# pulseox_brakeout_LCD_SCH.net
KiCad netlist of a schematic drawn in Altium Designer
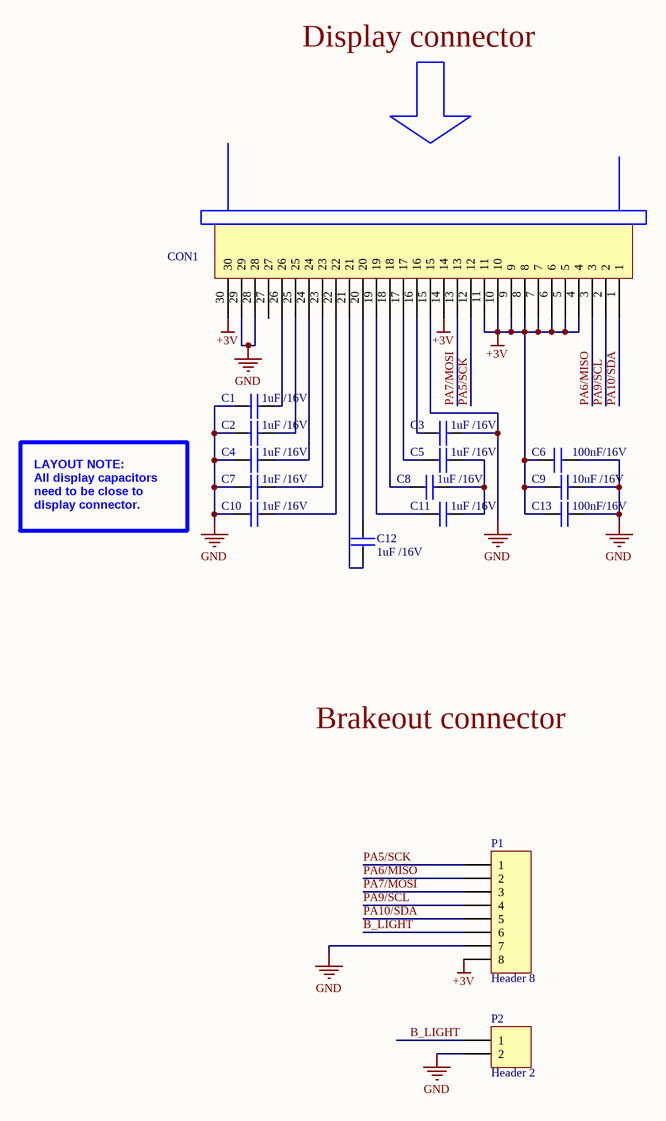
[diagram p0: pulseox_brakeout_LCD_SCH.SchDoc]

(export (version "E")
  (design (tool "Eeschema 10.0.6"))
  (components
    (comp (ref "C1")
      (value "1uF /16V")
      (footprint "CAP0805")
      (description "MURATA - GRM21BR71C105KA01L - CAP, MLCC, X7R, 1UF, 16V, 0805")
      (fields
        (field (name "MANUFACTURER") "MURATA")
        (field (name "MANUFACTURER PART NUMBER") "GRM21BR71C105KA01L")
      )
      (libsource (lib "Capacitors") (part "1uF /16V"))
    )
    (comp (ref "C2")
      (value "1uF /16V")
      (footprint "CAP0805")
      (description "MURATA - GRM21BR71C105KA01L - CAP, MLCC, X7R, 1UF, 16V, 0805")
      (fields
        (field (name "MANUFACTURER") "MURATA")
        (field (name "MANUFACTURER PART NUMBER") "GRM21BR71C105KA01L")
      )
      (libsource (lib "Capacitors") (part "1uF /16V"))
    )
    (comp (ref "C3")
      (value "1uF /16V")
      (footprint "CAP0805")
      (description "MURATA - GRM21BR71C105KA01L - CAP, MLCC, X7R, 1UF, 16V, 0805")
      (fields
        (field (name "MANUFACTURER") "MURATA")
        (field (name "MANUFACTURER PART NUMBER") "GRM21BR71C105KA01L")
      )
      (libsource (lib "Capacitors") (part "1uF /16V"))
    )
    (comp (ref "C4")
      (value "1uF /16V")
      (footprint "CAP0805")
      (description "MURATA - GRM21BR71C105KA01L - CAP, MLCC, X7R, 1UF, 16V, 0805")
      (fields
        (field (name "MANUFACTURER") "MURATA")
        (field (name "MANUFACTURER PART NUMBER") "GRM21BR71C105KA01L")
      )
      (libsource (lib "Capacitors") (part "1uF /16V"))
    )
    (comp (ref "C5")
      (value "1uF /16V")
      (footprint "CAP0805")
      (description "MURATA - GRM21BR71C105KA01L - CAP, MLCC, X7R, 1UF, 16V, 0805")
      (fields
        (field (name "MANUFACTURER") "MURATA")
        (field (name "MANUFACTURER PART NUMBER") "GRM21BR71C105KA01L")
      )
      (libsource (lib "Capacitors") (part "1uF /16V"))
    )
    (comp (ref "C6")
      (value "100nF/16V")
      (footprint "CAP0805")
      (description "MURATA - GRM219R71C104KA01D - CAP, MLCC, X7R, 0.1UF, 16V, 0805")
      (fields
        (field (name "MANUFACTURER") "MURATA")
        (field (name "MANUFACTURER PART NUMBER") "GRM219R71C104KA01D")
      )
      (libsource (lib "Capacitors") (part "100nF 16V 0805"))
    )
    (comp (ref "C7")
      (value "1uF /16V")
      (footprint "CAP0805")
      (description "MURATA - GRM21BR71C105KA01L - CAP, MLCC, X7R, 1UF, 16V, 0805")
      (fields
        (field (name "MANUFACTURER") "MURATA")
        (field (name "MANUFACTURER PART NUMBER") "GRM21BR71C105KA01L")
      )
      (libsource (lib "Capacitors") (part "1uF /16V"))
    )
    (comp (ref "C8")
      (value "1uF /16V")
      (footprint "CAP0805")
      (description "MURATA - GRM21BR71C105KA01L - CAP, MLCC, X7R, 1UF, 16V, 0805")
      (fields
        (field (name "MANUFACTURER") "MURATA")
        (field (name "MANUFACTURER PART NUMBER") "GRM21BR71C105KA01L")
      )
      (libsource (lib "Capacitors") (part "1uF /16V"))
    )
    (comp (ref "C9")
      (value "10uF /16V")
      (footprint "CAP0805")
      (description "TDK - CGA4J1X5R1C106K125AC - CAP, MLCC, X5R, 10UF, 16V, 0805")
      (fields
        (field (name "MANUFACTURER") "TDK")
        (field (name "MANUFACTURER PART NUMBER") "CGA4J1X5R1C106K125AC")
      )
      (libsource (lib "Capacitors") (part "10uF /16V"))
    )
    (comp (ref "C10")
      (value "1uF /16V")
      (footprint "CAP0805")
      (description "MURATA - GRM21BR71C105KA01L - CAP, MLCC, X7R, 1UF, 16V, 0805")
      (fields
        (field (name "MANUFACTURER") "MURATA")
        (field (name "MANUFACTURER PART NUMBER") "GRM21BR71C105KA01L")
      )
      (libsource (lib "Capacitors") (part "1uF /16V"))
    )
    (comp (ref "C11")
      (value "1uF /16V")
      (footprint "CAP0805")
      (description "MURATA - GRM21BR71C105KA01L - CAP, MLCC, X7R, 1UF, 16V, 0805")
      (fields
        (field (name "MANUFACTURER") "MURATA")
        (field (name "MANUFACTURER PART NUMBER") "GRM21BR71C105KA01L")
      )
      (libsource (lib "Capacitors") (part "1uF /16V"))
    )
    (comp (ref "C12")
      (value "1uF /16V")
      (footprint "CAP0805")
      (description "MURATA - GRM21BR71C105KA01L - CAP, MLCC, X7R, 1UF, 16V, 0805")
      (fields
        (field (name "MANUFACTURER") "MURATA")
        (field (name "MANUFACTURER PART NUMBER") "GRM21BR71C105KA01L")
      )
      (libsource (lib "Capacitors") (part "1uF /16V"))
    )
    (comp (ref "C13")
      (value "100nF/16V")
      (footprint "CAP0805")
      (description "MURATA - GRM219R71C104KA01D - CAP, MLCC, X7R, 0.1UF, 16V, 0805")
      (fields
        (field (name "MANUFACTURER") "MURATA")
        (field (name "MANUFACTURER PART NUMBER") "GRM219R71C104KA01D")
      )
      (libsource (lib "Capacitors") (part "100nF 16V 0805"))
    )
    (comp (ref "CON1")
      (value "3-1734592-0")
      (footprint "FPC P0.5mm SMT")
      (description "AMP - TE CONNECTIVITY - 3-1734592-0 - CONNECTOR, FFC / FPC, 0.5MM, 30WAY")
      (fields (field (name "MANUFACTURER") "AMP - TE CONNECTIVITY"))
      (libsource (lib "FFC-FPC board connectors") (part "3-1734592-0"))
    )
    (comp (ref "P1")
      (value "Header 8")
      (footprint "HDR1X8")
      (description "Header, 8-Pin")
      (fields (field (name "PUBLISHER") "Altium Limited"))
      (libsource (lib "Miscellaneous Connectors") (part "Header 8"))
    )
    (comp (ref "P2")
      (value "Header 2")
      (footprint "HDR1X2")
      (description "Header, 2-Pin")
      (fields (field (name "PUBLISHER") "Altium Limited"))
      (libsource (lib "Miscellaneous Connectors") (part "Header 2"))
    )
  )
  (nets
    (net (code "1") (name "+3V") (class "Default")
      (node (ref "C13") (pin "1") (pinfunction "1_1") (pintype "passive"))
      (node (ref "C6") (pin "1") (pinfunction "1_1") (pintype "passive"))
      (node (ref "C9") (pin "1") (pinfunction "1_1") (pintype "passive"))
      (node (ref "CON1") (pin "10") (pinfunction "10_10") (pintype "open_collector"))
      (node (ref "CON1") (pin "11") (pinfunction "11_11") (pintype "open_collector"))
      (node (ref "CON1") (pin "14") (pinfunction "14_14") (pintype "open_collector"))
      (node (ref "CON1") (pin "30") (pinfunction "30_30") (pintype "open_collector"))
      (node (ref "CON1") (pin "4") (pinfunction "4_4") (pintype "open_collector"))
      (node (ref "CON1") (pin "5") (pinfunction "5_5") (pintype "open_collector"))
      (node (ref "CON1") (pin "6") (pinfunction "6_6") (pintype "open_collector"))
      (node (ref "CON1") (pin "7") (pinfunction "7_7") (pintype "open_collector"))
      (node (ref "CON1") (pin "8") (pinfunction "8_8") (pintype "open_collector"))
      (node (ref "CON1") (pin "9") (pinfunction "9_9") (pintype "open_collector"))
      (node (ref "P1") (pin "8") (pinfunction "8_8") (pintype "passive"))
    )
    (net (code "2") (name "/B_LIGHT") (class "Default")
      (node (ref "P1") (pin "6") (pinfunction "6_6") (pintype "passive"))
      (node (ref "P2") (pin "1") (pinfunction "1_1") (pintype "passive"))
    )
    (net (code "3") (name "/PA5{slash}SCK") (class "Default")
      (node (ref "CON1") (pin "12") (pinfunction "12_12") (pintype "open_collector"))
      (node (ref "P1") (pin "1") (pinfunction "1_1") (pintype "passive"))
    )
    (net (code "4") (name "/PA6{slash}MISO") (class "Default")
      (node (ref "CON1") (pin "3") (pinfunction "3_3") (pintype "open_collector"))
      (node (ref "P1") (pin "2") (pinfunction "2_2") (pintype "passive"))
    )
    (net (code "5") (name "/PA7{slash}MOSI") (class "Default")
      (node (ref "CON1") (pin "13") (pinfunction "13_13") (pintype "open_collector"))
      (node (ref "P1") (pin "3") (pinfunction "3_3") (pintype "passive"))
    )
    (net (code "6") (name "/PA9{slash}SCL") (class "Default")
      (node (ref "CON1") (pin "2") (pinfunction "2_2") (pintype "open_collector"))
      (node (ref "P1") (pin "4") (pinfunction "4_4") (pintype "passive"))
    )
    (net (code "7") (name "/PA10{slash}SDA") (class "Default")
      (node (ref "CON1") (pin "1") (pinfunction "1_1") (pintype "open_collector"))
      (node (ref "P1") (pin "5") (pinfunction "5_5") (pintype "passive"))
    )
    (net (code "8") (name "GND") (class "Default")
      (node (ref "C1") (pin "1") (pinfunction "1_1") (pintype "passive"))
      (node (ref "C10") (pin "1") (pinfunction "1_1") (pintype "passive"))
      (node (ref "C13") (pin "2") (pinfunction "2_2") (pintype "passive"))
      (node (ref "C2") (pin "1") (pinfunction "1_1") (pintype "passive"))
      (node (ref "C3") (pin "2") (pinfunction "2_2") (pintype "passive"))
      (node (ref "C4") (pin "1") (pinfunction "1_1") (pintype "passive"))
      (node (ref "C6") (pin "2") (pinfunction "2_2") (pintype "passive"))
      (node (ref "C7") (pin "1") (pinfunction "1_1") (pintype "passive"))
      (node (ref "C9") (pin "2") (pinfunction "2_2") (pintype "passive"))
      (node (ref "CON1") (pin "15") (pinfunction "15_15") (pintype "open_collector"))
      (node (ref "CON1") (pin "28") (pinfunction "28_28") (pintype "open_collector"))
      (node (ref "CON1") (pin "29") (pinfunction "29_29") (pintype "open_collector"))
      (node (ref "P1") (pin "7") (pinfunction "7_7") (pintype "passive"))
      (node (ref "P2") (pin "2") (pinfunction "2_2") (pintype "passive"))
    )
    (net (code "9") (name "Net-(C1-Pad2)") (class "Default")
      (node (ref "C1") (pin "2") (pinfunction "2_2") (pintype "passive"))
      (node (ref "CON1") (pin "26") (pinfunction "26_26") (pintype "open_collector"))
    )
    (net (code "10") (name "Net-(C2-Pad2)") (class "Default")
      (node (ref "C2") (pin "2") (pinfunction "2_2") (pintype "passive"))
      (node (ref "CON1") (pin "25") (pinfunction "25_25") (pintype "open_collector"))
    )
    (net (code "11") (name "Net-(C3-Pad1)") (class "Default")
      (node (ref "C3") (pin "1") (pinfunction "1_1") (pintype "passive"))
      (node (ref "CON1") (pin "16") (pinfunction "16_16") (pintype "open_collector"))
    )
    (net (code "12") (name "Net-(C4-Pad2)") (class "Default")
      (node (ref "C4") (pin "2") (pinfunction "2_2") (pintype "passive"))
      (node (ref "CON1") (pin "24") (pinfunction "24_24") (pintype "open_collector"))
    )
    (net (code "13") (name "Net-(C5-Pad1)") (class "Default")
      (node (ref "C5") (pin "1") (pinfunction "1_1") (pintype "passive"))
      (node (ref "CON1") (pin "17") (pinfunction "17_17") (pintype "open_collector"))
    )
    (net (code "14") (name "Net-(C7-Pad2)") (class "Default")
      (node (ref "C7") (pin "2") (pinfunction "2_2") (pintype "passive"))
      (node (ref "CON1") (pin "23") (pinfunction "23_23") (pintype "open_collector"))
    )
    (net (code "15") (name "Net-(C8-Pad1)") (class "Default")
      (node (ref "C8") (pin "1") (pinfunction "1_1") (pintype "passive"))
      (node (ref "CON1") (pin "18") (pinfunction "18_18") (pintype "open_collector"))
    )
    (net (code "16") (name "Net-(C10-Pad2)") (class "Default")
      (node (ref "C10") (pin "2") (pinfunction "2_2") (pintype "passive"))
      (node (ref "CON1") (pin "22") (pinfunction "22_22") (pintype "open_collector"))
    )
    (net (code "17") (name "Net-(C11-Pad1)") (class "Default")
      (node (ref "C11") (pin "1") (pinfunction "1_1") (pintype "passive"))
      (node (ref "CON1") (pin "19") (pinfunction "19_19") (pintype "open_collector"))
    )
    (net (code "18") (name "Net-(C11-Pad2)") (class "Default")
      (node (ref "C11") (pin "2") (pinfunction "2_2") (pintype "passive"))
      (node (ref "C5") (pin "2") (pinfunction "2_2") (pintype "passive"))
      (node (ref "C8") (pin "2") (pinfunction "2_2") (pintype "passive"))
    )
    (net (code "19") (name "Net-(C12-Pad1)") (class "Default")
      (node (ref "C12") (pin "1") (pinfunction "1_1") (pintype "passive"))
      (node (ref "CON1") (pin "21") (pinfunction "21_21") (pintype "open_collector"))
    )
    (net (code "20") (name "Net-(C12-Pad2)") (class "Default")
      (node (ref "C12") (pin "2") (pinfunction "2_2") (pintype "passive"))
      (node (ref "CON1") (pin "20") (pinfunction "20_20") (pintype "open_collector"))
    )
    (net (code "21") (name "unconnected-(CON1-Pad27)") (class "Default")
      (node (ref "CON1") (pin "27") (pinfunction "27_27") (pintype "open_collector"))
    )
  )
)
